# guitar_base.net
KiCad netlist of a schematic drawn in EAGLE
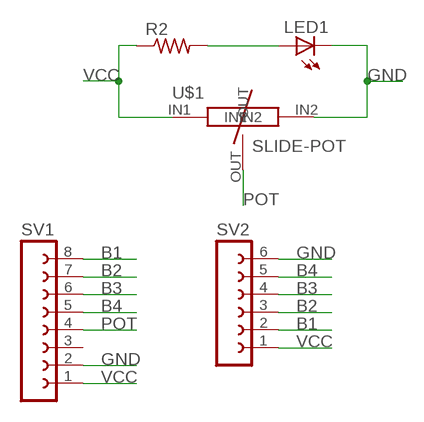
[diagram p0: schematic, sheet 1]

(export (version "E")
  (design (tool "Eeschema 10.0.6"))
  (components
    (comp (ref "LED1")
      (value "LED5MM")
      (footprint "eagle-import:LED5MM")
      (libsource (lib "eagle-import") (part "LED5MM"))
    )
    (comp (ref "R2")
      (value "R-US_0207/7")
      (footprint "eagle-import:0207_7")
      (libsource (lib "eagle-import") (part "R-US_0207/7"))
    )
    (comp (ref "SV1")
      (value "FE08-1")
      (footprint "eagle-import:FE08")
      (libsource (lib "eagle-import") (part "FE08-1"))
    )
    (comp (ref "SV2")
      (value "FE06-1")
      (footprint "eagle-import:FE06")
      (libsource (lib "eagle-import") (part "FE06-1"))
    )
    (comp (ref "U$1")
      (value "SLIDE-POT")
      (footprint "eagle-import:SLIDE-POT")
      (libsource (lib "eagle-import") (part "SLIDE-POT"))
    )
  )
  (nets
    (net (code "1") (name "/B1") (class "Default")
      (node (ref "SV1") (pin "8") (pinfunction "8_8") (pintype "passive"))
      (node (ref "SV2") (pin "2") (pinfunction "2_2") (pintype "passive"))
    )
    (net (code "2") (name "/B2") (class "Default")
      (node (ref "SV1") (pin "7") (pinfunction "7_7") (pintype "passive"))
      (node (ref "SV2") (pin "3") (pinfunction "3_3") (pintype "passive"))
    )
    (net (code "3") (name "/B3") (class "Default")
      (node (ref "SV1") (pin "6") (pinfunction "6_6") (pintype "passive"))
      (node (ref "SV2") (pin "4") (pinfunction "4_4") (pintype "passive"))
    )
    (net (code "4") (name "/B4") (class "Default")
      (node (ref "SV1") (pin "5") (pinfunction "5_5") (pintype "passive"))
      (node (ref "SV2") (pin "5") (pinfunction "5_5") (pintype "passive"))
    )
    (net (code "5") (name "/GND") (class "Default")
      (node (ref "LED1") (pin "K") (pinfunction "C_K") (pintype "passive"))
      (node (ref "SV1") (pin "2") (pinfunction "2_2") (pintype "passive"))
      (node (ref "SV2") (pin "6") (pinfunction "6_6") (pintype "passive"))
      (node (ref "U$1") (pin "IN2") (pinfunction "IN2_IN2") (pintype "bidirectional"))
    )
    (net (code "6") (name "/POT") (class "Default")
      (node (ref "SV1") (pin "4") (pinfunction "4_4") (pintype "passive"))
      (node (ref "U$1") (pin "OUT") (pinfunction "OUT_OUT") (pintype "bidirectional"))
    )
    (net (code "7") (name "/VCC") (class "Default")
      (node (ref "R2") (pin "1") (pinfunction "1_1") (pintype "passive"))
      (node (ref "SV1") (pin "1") (pinfunction "1_1") (pintype "passive"))
      (node (ref "SV2") (pin "1") (pinfunction "1_1") (pintype "passive"))
      (node (ref "U$1") (pin "IN1") (pinfunction "IN1_IN1") (pintype "bidirectional"))
    )
    (net (code "8") (name "Net-(LED1-PadA)") (class "Default")
      (node (ref "LED1") (pin "A") (pinfunction "A_A") (pintype "passive"))
      (node (ref "R2") (pin "2") (pinfunction "2_2") (pintype "passive"))
    )
    (net (code "9") (name "unconnected-(SV1-Pad3)") (class "Default")
      (node (ref "SV1") (pin "3") (pinfunction "3_3") (pintype "passive"))
    )
  )
)
